# MCUs.net
KiCad netlist of a schematic drawn in Altium Designer
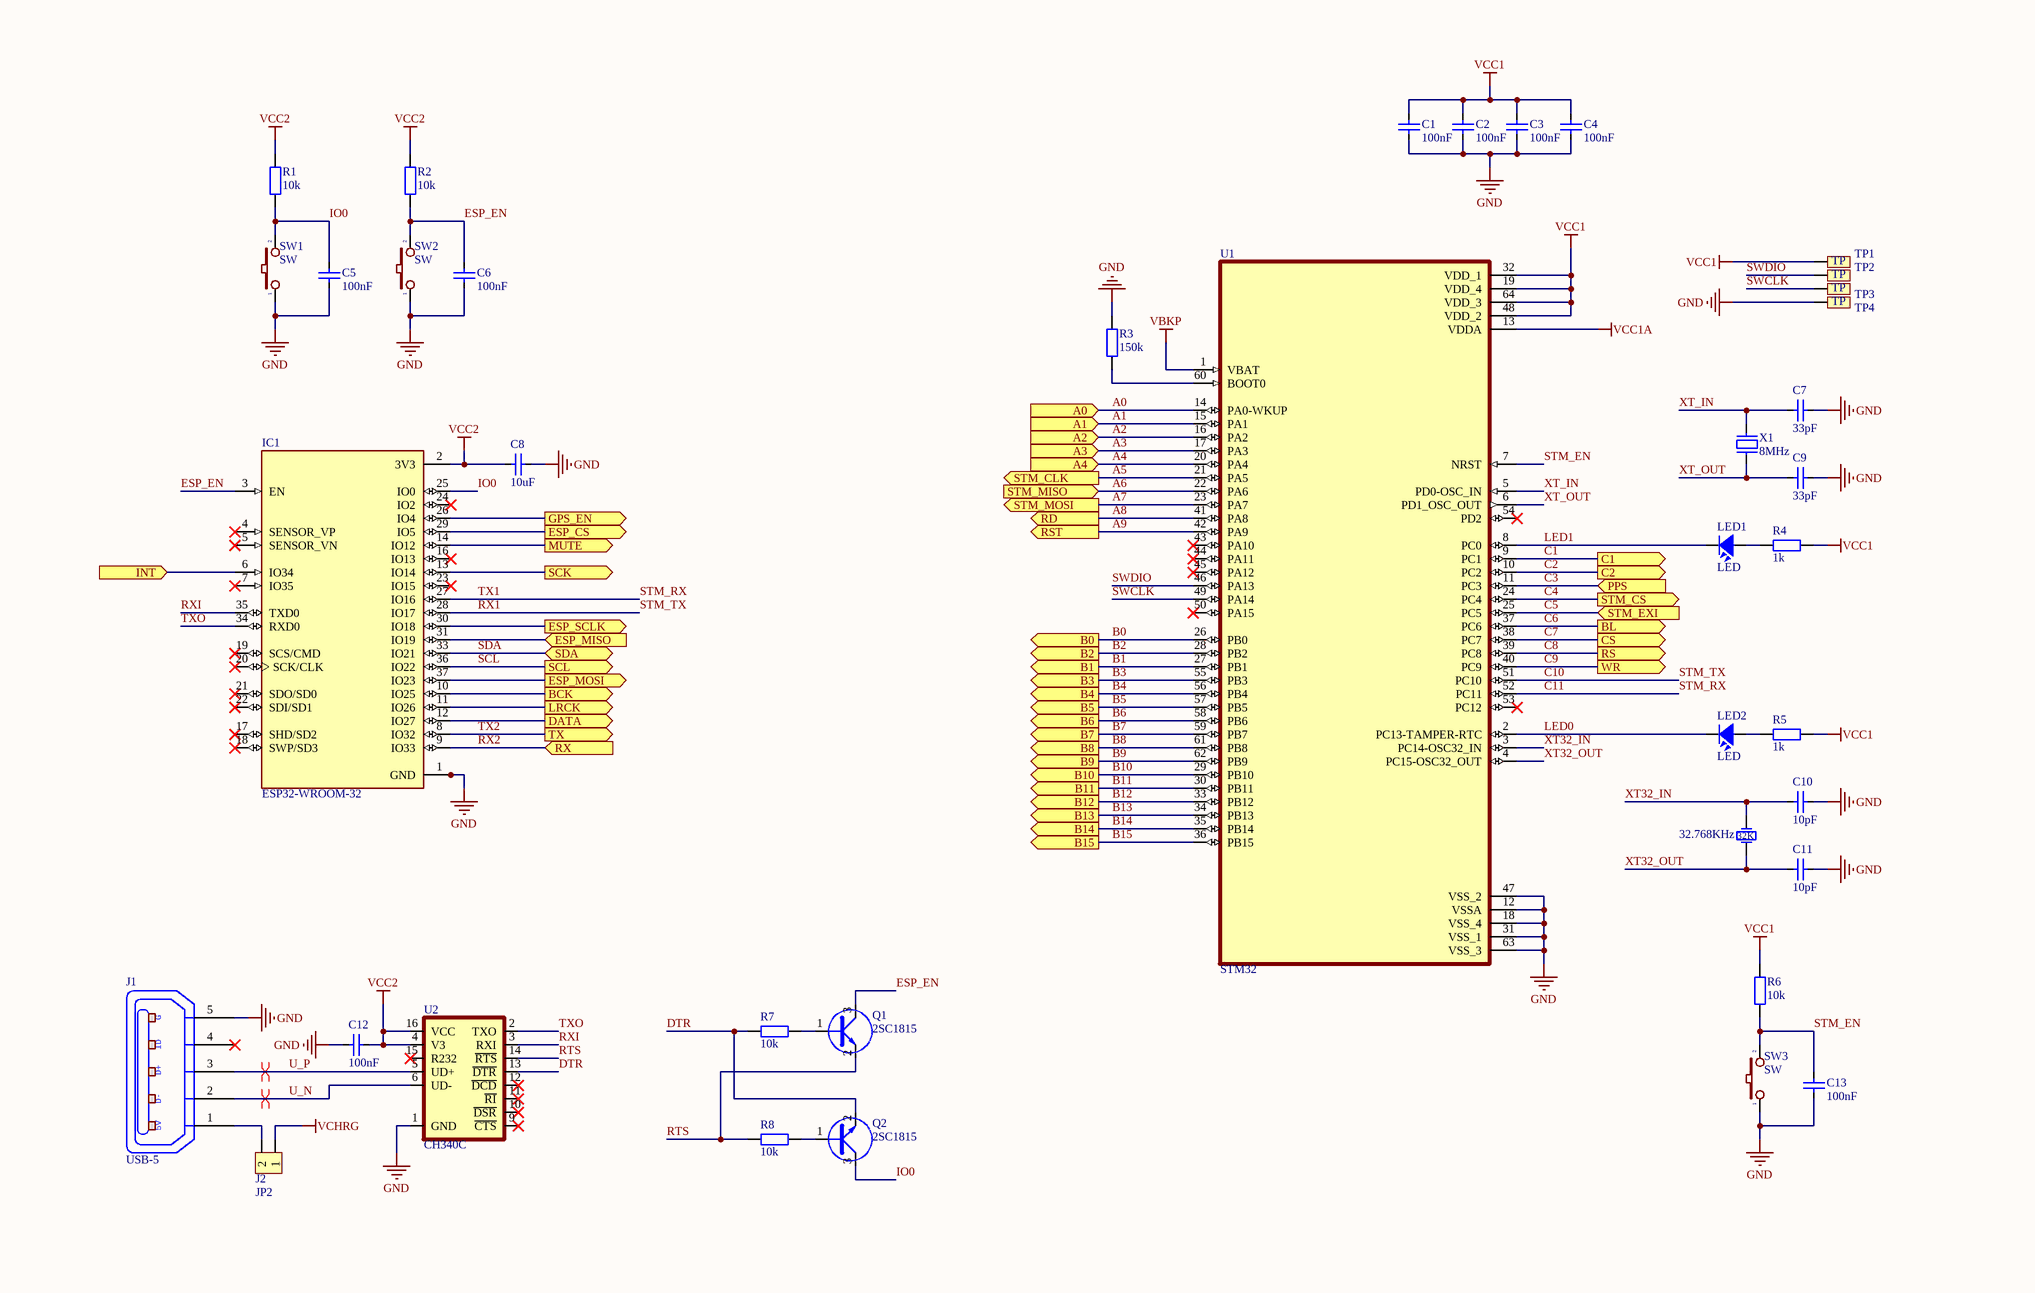
[diagram p0: MCUs.SchDoc]

(export (version "E")
  (design (tool "Eeschema 10.0.6"))
  (components
    (comp (ref "C1")
      (value "100nF")
      (footprint "CAP_0603")
      (description "Capacitor")
      (fields (field (name "PUBLISHER") "Altium Limited"))
      (libsource (lib "My Library") (part "CapSMD"))
    )
    (comp (ref "C2")
      (value "100nF")
      (footprint "CAP_0603")
      (description "Capacitor")
      (fields (field (name "PUBLISHER") "Altium Limited"))
      (libsource (lib "My Library") (part "CapSMD"))
    )
    (comp (ref "C3")
      (value "100nF")
      (footprint "CAP_0603")
      (description "Capacitor")
      (fields (field (name "PUBLISHER") "Altium Limited"))
      (libsource (lib "My Library") (part "CapSMD"))
    )
    (comp (ref "C4")
      (value "100nF")
      (footprint "CAP_0603")
      (description "Capacitor")
      (fields (field (name "PUBLISHER") "Altium Limited"))
      (libsource (lib "My Library") (part "CapSMD"))
    )
    (comp (ref "C5")
      (value "100nF")
      (footprint "CAP_0603")
      (description "Capacitor")
      (fields (field (name "PUBLISHER") "Altium Limited"))
      (libsource (lib "My Library") (part "CapSMD"))
    )
    (comp (ref "C6")
      (value "100nF")
      (footprint "CAP_0603")
      (description "Capacitor")
      (fields (field (name "PUBLISHER") "Altium Limited"))
      (libsource (lib "My Library") (part "CapSMD"))
    )
    (comp (ref "C7")
      (value "33pF")
      (footprint "CAP_0603")
      (description "Capacitor")
      (fields (field (name "PUBLISHER") "Altium Limited"))
      (libsource (lib "My Library") (part "CapSMD"))
    )
    (comp (ref "C8")
      (value "10uF")
      (footprint "CAP_0603")
      (description "Capacitor")
      (fields (field (name "PUBLISHER") "Altium Limited"))
      (libsource (lib "My Library") (part "CapSMD"))
    )
    (comp (ref "C9")
      (value "33pF")
      (footprint "CAP_0603")
      (description "Capacitor")
      (fields (field (name "PUBLISHER") "Altium Limited"))
      (libsource (lib "My Library") (part "CapSMD"))
    )
    (comp (ref "C10")
      (value "10pF")
      (footprint "CAP_0603")
      (description "Capacitor")
      (fields (field (name "PUBLISHER") "Altium Limited"))
      (libsource (lib "My Library") (part "CapSMD"))
    )
    (comp (ref "C11")
      (value "10pF")
      (footprint "CAP_0603")
      (description "Capacitor")
      (fields (field (name "PUBLISHER") "Altium Limited"))
      (libsource (lib "My Library") (part "CapSMD"))
    )
    (comp (ref "C12")
      (value "100nF")
      (footprint "CAP_0603")
      (description "Capacitor")
      (fields (field (name "PUBLISHER") "Altium Limited"))
      (libsource (lib "My Library") (part "CapSMD"))
    )
    (comp (ref "C13")
      (value "100nF")
      (footprint "CAP_0603")
      (description "Capacitor")
      (fields (field (name "PUBLISHER") "Altium Limited"))
      (libsource (lib "My Library") (part "CapSMD"))
    )
    (comp (ref "IC1")
      (value "ESP32-WROOM-32")
      (footprint "MODULE_ESP32-WROOM-32")
      (description "Bluetooth, WiFi Transceiver Module 2.4GHz ~ 2.5GHz Surface Mount")
      (fields (field (name "MF") "Espressif Systems") (field (name "DIGI-KEY_PART_NUMBER") "1904-1010-1-ND"))
      (libsource (lib "My Library") (part "ESP32-WROOM-32"))
    )
    (comp (ref "J1")
      (value "USB-5")
      (footprint "USB-M1")
      (fields
        (field (name "MANUFACTURER") "FCI")
        (field (name "MANUFACTURER PART NUMBER") "10118193-0001LF")
        (field (name ".CREATOR") "MM")
        (field (name ".CHECKED PCB") "RF")
        (field (name ".CHECKED SCH") "MM")
      )
      (libsource (lib "My Library") (part "USB-5"))
    )
    (comp (ref "J2")
      (value "JP2")
      (footprint "JP2-CLOSED")
      (description "WR-PHD 2.54 mm Angled Socket Header")
      (fields
        (field (name "MANUFACTURER") "Würth Elektronik eiSos GmbH")
        (field (name "PARTNO") "613002143121")
        (field (name "CREATED BY") "Karrer Zheng")
      )
      (libsource (lib "My Library") (part "JP2"))
    )
    (comp (ref "LED1")
      (value "LED")
      (footprint "LED-0805-Blue")
      (description "LED Single colour Green and Red")
      (libsource (lib "My Library") (part "LED"))
    )
    (comp (ref "LED2")
      (value "LED")
      (footprint "LED-0805-Green")
      (description "LED Single colour Green and Red")
      (libsource (lib "My Library") (part "LED"))
    )
    (comp (ref "Q1")
      (value "2SC1815")
      (footprint "SOT23D")
      (description "NPN 600mW, ECB")
      (libsource (lib "") (part "C1815_1"))
    )
    (comp (ref "Q2")
      (value "2SC1815")
      (footprint "SOT23D")
      (description "NPN 600mW, ECB")
      (libsource (lib "My Library") (part "C1815"))
    )
    (comp (ref "R1")
      (value "10k")
      (footprint "RES-SMD-0603")
      (description "Resistor SMD")
      (fields
        (field (name "MANUFACTURER") "Generic Components")
        (field (name "PUBLISHER") "Altium Hobart Technology Centre")
      )
      (libsource (lib "My Library") (part "Resistor - SMD"))
    )
    (comp (ref "R2")
      (value "10k")
      (footprint "RES-SMD-0603")
      (description "Resistor SMD")
      (fields
        (field (name "MANUFACTURER") "Generic Components")
        (field (name "PUBLISHER") "Altium Hobart Technology Centre")
      )
      (libsource (lib "My Library") (part "Resistor - SMD"))
    )
    (comp (ref "R3")
      (value "150k")
      (footprint "RES-SMD-0603")
      (description "Resistor SMD")
      (fields
        (field (name "MANUFACTURER") "Generic Components")
        (field (name "PUBLISHER") "Altium Hobart Technology Centre")
      )
      (libsource (lib "My Library") (part "Resistor - SMD"))
    )
    (comp (ref "R4")
      (value "1k")
      (footprint "RES-SMD-0603")
      (description "Resistor SMD")
      (fields
        (field (name "MANUFACTURER") "Generic Components")
        (field (name "PUBLISHER") "Altium Hobart Technology Centre")
      )
      (libsource (lib "My Library") (part "Resistor - SMD"))
    )
    (comp (ref "R5")
      (value "1k")
      (footprint "RES-SMD-0603")
      (description "Resistor SMD")
      (fields
        (field (name "MANUFACTURER") "Generic Components")
        (field (name "PUBLISHER") "Altium Hobart Technology Centre")
      )
      (libsource (lib "My Library") (part "Resistor - SMD"))
    )
    (comp (ref "R6")
      (value "10k")
      (footprint "RES-SMD-0603")
      (description "Resistor SMD")
      (fields
        (field (name "MANUFACTURER") "Generic Components")
        (field (name "PUBLISHER") "Altium Hobart Technology Centre")
      )
      (libsource (lib "My Library") (part "Resistor - SMD"))
    )
    (comp (ref "R7")
      (value "10k")
      (footprint "RES-SMD-0603")
      (description "Resistor SMD")
      (fields
        (field (name "MANUFACTURER") "Generic Components")
        (field (name "PUBLISHER") "Altium Hobart Technology Centre")
      )
      (libsource (lib "My Library") (part "Resistor - SMD"))
    )
    (comp (ref "R8")
      (value "10k")
      (footprint "RES-SMD-0603")
      (description "Resistor SMD")
      (fields
        (field (name "MANUFACTURER") "Generic Components")
        (field (name "PUBLISHER") "Altium Hobart Technology Centre")
      )
      (libsource (lib "My Library") (part "Resistor - SMD"))
    )
    (comp (ref "SW1")
      (value "SW")
      (footprint "SW 3x2x4")
      (description "Switch button 2 pin")
      (libsource (lib "My Library") (part "SW2"))
    )
    (comp (ref "SW2")
      (value "SW")
      (footprint "SW 3x2x4")
      (description "Switch button 2 pin")
      (libsource (lib "My Library") (part "SW2"))
    )
    (comp (ref "SW3")
      (value "SW")
      (footprint "SW 3x2x4")
      (description "Switch button 2 pin")
      (libsource (lib "My Library") (part "SW2"))
    )
    (comp (ref "TP1")
      (value "TP")
      (footprint "TP_SMD")
      (description "CONNECT 1")
      (libsource (lib "My Library") (part "TP"))
    )
    (comp (ref "TP2")
      (value "TP")
      (footprint "TP_SMD")
      (description "CONNECT 1")
      (libsource (lib "My Library") (part "TP"))
    )
    (comp (ref "TP3")
      (value "TP")
      (footprint "TP_SMD")
      (description "CONNECT 1")
      (libsource (lib "My Library") (part "TP"))
    )
    (comp (ref "TP4")
      (value "TP")
      (footprint "TP_SMD")
      (description "CONNECT 1")
      (libsource (lib "My Library") (part "TP"))
    )
    (comp (ref "U1")
      (value "STM32")
      (footprint "LQFP 64")
      (description "STM32 ARM-based 32-bit MCU 72MHz 256KB")
      (libsource (lib "My Library") (part "STM32F103RCT6"))
    )
    (comp (ref "U2")
      (value "CH340C")
      (footprint "SOP-16")
      (description "USB to serial chip CH340")
      (fields (field (name "MF") "WCH"))
      (libsource (lib "My Library") (part "CH340C"))
    )
    (comp (ref "X1")
      (value "8MHz")
      (footprint "XT2")
      (description "Crystal For all Crystal 2pin.")
      (libsource (lib "My Library") (part "XT2"))
    )
    (comp (ref "Y1")
      (value "32.768KHz")
      (footprint "XTAL32K")
      (description "Crystal Oscillator")
      (fields (field (name "PUBLISHER") "Altium Limited"))
      (libsource (lib "My Library") (part "XTAL/32KHz"))
    )
  )
  (nets
    (net (code "1") (name "/A0") (class "Default")
      (node (ref "U1") (pin "14") (pinfunction "PA0-WKUP_14") (pintype "bidirectional"))
    )
    (net (code "2") (name "/A1") (class "Default")
      (node (ref "U1") (pin "15") (pinfunction "PA1_15") (pintype "bidirectional"))
    )
    (net (code "3") (name "/A2") (class "Default")
      (node (ref "U1") (pin "16") (pinfunction "PA2_16") (pintype "bidirectional"))
    )
    (net (code "4") (name "/A3") (class "Default")
      (node (ref "U1") (pin "17") (pinfunction "PA3_17") (pintype "bidirectional"))
    )
    (net (code "5") (name "/A4") (class "Default")
      (node (ref "U1") (pin "20") (pinfunction "PA4_20") (pintype "bidirectional"))
    )
    (net (code "6") (name "/A5") (class "Default")
      (node (ref "U1") (pin "21") (pinfunction "PA5_21") (pintype "bidirectional"))
    )
    (net (code "7") (name "/A6") (class "Default")
      (node (ref "U1") (pin "22") (pinfunction "PA6_22") (pintype "bidirectional"))
    )
    (net (code "8") (name "/A7") (class "Default")
      (node (ref "U1") (pin "23") (pinfunction "PA7_23") (pintype "bidirectional"))
    )
    (net (code "9") (name "/A8") (class "Default")
      (node (ref "U1") (pin "41") (pinfunction "PA8_41") (pintype "bidirectional"))
    )
    (net (code "10") (name "/A9") (class "Default")
      (node (ref "U1") (pin "42") (pinfunction "PA9_42") (pintype "bidirectional"))
    )
    (net (code "11") (name "/B0") (class "Default")
      (node (ref "U1") (pin "26") (pinfunction "PB0_26") (pintype "bidirectional"))
    )
    (net (code "12") (name "/B1") (class "Default")
      (node (ref "U1") (pin "27") (pinfunction "PB1_27") (pintype "bidirectional"))
    )
    (net (code "13") (name "/B2") (class "Default")
      (node (ref "U1") (pin "28") (pinfunction "PB2_28") (pintype "bidirectional"))
    )
    (net (code "14") (name "/B3") (class "Default")
      (node (ref "U1") (pin "55") (pinfunction "PB3_55") (pintype "bidirectional"))
    )
    (net (code "15") (name "/B4") (class "Default")
      (node (ref "U1") (pin "56") (pinfunction "PB4_56") (pintype "bidirectional"))
    )
    (net (code "16") (name "/B5") (class "Default")
      (node (ref "U1") (pin "57") (pinfunction "PB5_57") (pintype "bidirectional"))
    )
    (net (code "17") (name "/B6") (class "Default")
      (node (ref "U1") (pin "58") (pinfunction "PB6_58") (pintype "bidirectional"))
    )
    (net (code "18") (name "/B7") (class "Default")
      (node (ref "U1") (pin "59") (pinfunction "PB7_59") (pintype "bidirectional"))
    )
    (net (code "19") (name "/B8") (class "Default")
      (node (ref "U1") (pin "61") (pinfunction "PB8_61") (pintype "bidirectional"))
    )
    (net (code "20") (name "/B9") (class "Default")
      (node (ref "U1") (pin "62") (pinfunction "PB9_62") (pintype "bidirectional"))
    )
    (net (code "21") (name "/B10") (class "Default")
      (node (ref "U1") (pin "29") (pinfunction "PB10_29") (pintype "bidirectional"))
    )
    (net (code "22") (name "/B11") (class "Default")
      (node (ref "U1") (pin "30") (pinfunction "PB11_30") (pintype "bidirectional"))
    )
    (net (code "23") (name "/B12") (class "Default")
      (node (ref "U1") (pin "33") (pinfunction "PB12_33") (pintype "bidirectional"))
    )
    (net (code "24") (name "/B13") (class "Default")
      (node (ref "U1") (pin "34") (pinfunction "PB13_34") (pintype "bidirectional"))
    )
    (net (code "25") (name "/B14") (class "Default")
      (node (ref "U1") (pin "35") (pinfunction "PB14_35") (pintype "bidirectional"))
    )
    (net (code "26") (name "/B15") (class "Default")
      (node (ref "U1") (pin "36") (pinfunction "PB15_36") (pintype "bidirectional"))
    )
    (net (code "27") (name "/BCK") (class "Default")
      (node (ref "IC1") (pin "10") (pinfunction "IO25_10") (pintype "bidirectional"))
    )
    (net (code "28") (name "/C1") (class "Default")
      (node (ref "U1") (pin "9") (pinfunction "PC1_9") (pintype "bidirectional"))
    )
    (net (code "29") (name "/C2") (class "Default")
      (node (ref "U1") (pin "10") (pinfunction "PC2_10") (pintype "bidirectional"))
    )
    (net (code "30") (name "/C3") (class "Default")
      (node (ref "U1") (pin "11") (pinfunction "PC3_11") (pintype "bidirectional"))
    )
    (net (code "31") (name "/C4") (class "Default")
      (node (ref "U1") (pin "24") (pinfunction "PC4_24") (pintype "bidirectional"))
    )
    (net (code "32") (name "/C5") (class "Default")
      (node (ref "U1") (pin "25") (pinfunction "PC5_25") (pintype "bidirectional"))
    )
    (net (code "33") (name "/C6") (class "Default")
      (node (ref "U1") (pin "37") (pinfunction "PC6_37") (pintype "bidirectional"))
    )
    (net (code "34") (name "/C7") (class "Default")
      (node (ref "U1") (pin "38") (pinfunction "PC7_38") (pintype "bidirectional"))
    )
    (net (code "35") (name "/C8") (class "Default")
      (node (ref "U1") (pin "39") (pinfunction "PC8_39") (pintype "bidirectional"))
    )
    (net (code "36") (name "/C9") (class "Default")
      (node (ref "U1") (pin "40") (pinfunction "PC9_40") (pintype "bidirectional"))
    )
    (net (code "37") (name "/C10") (class "Default")
      (node (ref "IC1") (pin "28") (pinfunction "IO17_28") (pintype "bidirectional"))
      (node (ref "U1") (pin "51") (pinfunction "PC10_51") (pintype "bidirectional"))
    )
    (net (code "38") (name "/C11") (class "Default")
      (node (ref "IC1") (pin "27") (pinfunction "IO16_27") (pintype "bidirectional"))
      (node (ref "U1") (pin "52") (pinfunction "PC11_52") (pintype "bidirectional"))
    )
    (net (code "39") (name "/DATA") (class "Default")
      (node (ref "IC1") (pin "12") (pinfunction "IO27_12") (pintype "bidirectional"))
    )
    (net (code "40") (name "/DTR") (class "Default")
      (node (ref "Q2") (pin "2") (pinfunction "E_2") (pintype "passive"))
      (node (ref "R7") (pin "2") (pinfunction "2_2") (pintype "passive"))
      (node (ref "U2") (pin "13") (pinfunction "~{DTR}_13") (pintype "bidirectional"))
    )
    (net (code "41") (name "/ESP_CS") (class "Default")
      (node (ref "IC1") (pin "29") (pinfunction "IO5_29") (pintype "bidirectional"))
    )
    (net (code "42") (name "/ESP_EN") (class "Default")
      (node (ref "C6") (pin "1") (pinfunction "1_1") (pintype "passive"))
      (node (ref "IC1") (pin "3") (pinfunction "EN_3") (pintype "input"))
      (node (ref "Q1") (pin "3") (pinfunction "C_3") (pintype "passive"))
      (node (ref "R2") (pin "1") (pinfunction "1_1") (pintype "passive"))
      (node (ref "SW2") (pin "2") (pinfunction "2_2") (pintype "passive"))
    )
    (net (code "43") (name "/ESP_MISO") (class "Default")
      (node (ref "IC1") (pin "31") (pinfunction "IO19_31") (pintype "bidirectional"))
    )
    (net (code "44") (name "/ESP_MOSI") (class "Default")
      (node (ref "IC1") (pin "37") (pinfunction "IO23_37") (pintype "bidirectional"))
    )
    (net (code "45") (name "/ESP_SCLK") (class "Default")
      (node (ref "IC1") (pin "30") (pinfunction "IO18_30") (pintype "bidirectional"))
    )
    (net (code "46") (name "/GPS_EN") (class "Default")
      (node (ref "IC1") (pin "26") (pinfunction "IO4_26") (pintype "bidirectional"))
    )
    (net (code "47") (name "/INT") (class "Default")
      (node (ref "IC1") (pin "6") (pinfunction "IO34_6") (pintype "input"))
    )
    (net (code "48") (name "/IO0") (class "Default")
      (node (ref "C5") (pin "1") (pinfunction "1_1") (pintype "passive"))
      (node (ref "IC1") (pin "25") (pinfunction "IO0_25") (pintype "bidirectional"))
      (node (ref "Q2") (pin "3") (pinfunction "C_3") (pintype "passive"))
      (node (ref "R1") (pin "1") (pinfunction "1_1") (pintype "passive"))
      (node (ref "SW1") (pin "2") (pinfunction "2_2") (pintype "passive"))
    )
    (net (code "49") (name "/LED0") (class "Default")
      (node (ref "LED2") (pin "2") (pinfunction "2_2") (pintype "passive"))
      (node (ref "U1") (pin "2") (pinfunction "PC13-TAMPER-RTC_2") (pintype "bidirectional"))
    )
    (net (code "50") (name "/LED1") (class "Default")
      (node (ref "LED1") (pin "2") (pinfunction "2_2") (pintype "passive"))
      (node (ref "U1") (pin "8") (pinfunction "PC0_8") (pintype "bidirectional"))
    )
    (net (code "51") (name "/LRCK") (class "Default")
      (node (ref "IC1") (pin "11") (pinfunction "IO26_11") (pintype "bidirectional"))
    )
    (net (code "52") (name "/MUTE") (class "Default")
      (node (ref "IC1") (pin "14") (pinfunction "IO12_14") (pintype "bidirectional"))
    )
    (net (code "53") (name "/RTS") (class "Default")
      (node (ref "Q1") (pin "2") (pinfunction "E_2") (pintype "passive"))
      (node (ref "R8") (pin "2") (pinfunction "2_2") (pintype "passive"))
      (node (ref "U2") (pin "14") (pinfunction "~{RTS}_14") (pintype "bidirectional"))
    )
    (net (code "54") (name "/RX2") (class "Default")
      (node (ref "IC1") (pin "9") (pinfunction "IO33_9") (pintype "bidirectional"))
    )
    (net (code "55") (name "/RXI") (class "Default")
      (node (ref "IC1") (pin "35") (pinfunction "TXD0_35") (pintype "bidirectional"))
      (node (ref "U2") (pin "3") (pinfunction "RXI_3") (pintype "bidirectional"))
    )
    (net (code "56") (name "/SCK") (class "Default")
      (node (ref "IC1") (pin "13") (pinfunction "IO14_13") (pintype "bidirectional"))
    )
    (net (code "57") (name "/SCL") (class "Default")
      (node (ref "IC1") (pin "36") (pinfunction "IO22_36") (pintype "bidirectional"))
    )
    (net (code "58") (name "/SDA") (class "Default")
      (node (ref "IC1") (pin "33") (pinfunction "IO21_33") (pintype "bidirectional"))
    )
    (net (code "59") (name "/STM_EN") (class "Default")
      (node (ref "C13") (pin "1") (pinfunction "1_1") (pintype "passive"))
      (node (ref "R6") (pin "1") (pinfunction "1_1") (pintype "passive"))
      (node (ref "SW3") (pin "2") (pinfunction "2_2") (pintype "passive"))
      (node (ref "U1") (pin "7") (pinfunction "NRST_7") (pintype "input"))
    )
    (net (code "60") (name "/SWCLK") (class "Default")
      (node (ref "TP3") (pin "1") (pinfunction "0_1") (pintype "passive"))
      (node (ref "U1") (pin "49") (pinfunction "PA14_49") (pintype "bidirectional"))
    )
    (net (code "61") (name "/SWDIO") (class "Default")
      (node (ref "TP2") (pin "1") (pinfunction "0_1") (pintype "passive"))
      (node (ref "U1") (pin "46") (pinfunction "PA13_46") (pintype "bidirectional"))
    )
    (net (code "62") (name "/TX2") (class "Default")
      (node (ref "IC1") (pin "8") (pinfunction "IO32_8") (pintype "bidirectional"))
    )
    (net (code "63") (name "/TXO") (class "Default")
      (node (ref "IC1") (pin "34") (pinfunction "RXD0_34") (pintype "bidirectional"))
      (node (ref "U2") (pin "2") (pinfunction "TXO_2") (pintype "bidirectional"))
    )
    (net (code "64") (name "/U_N") (class "Default")
      (node (ref "J1") (pin "2") (pinfunction "P2_2") (pintype "passive"))
      (node (ref "U2") (pin "6") (pinfunction "UD-_6") (pintype "bidirectional"))
    )
    (net (code "65") (name "/U_P") (class "Default")
      (node (ref "J1") (pin "3") (pinfunction "P3_3") (pintype "passive"))
      (node (ref "U2") (pin "5") (pinfunction "UD+_5") (pintype "bidirectional"))
    )
    (net (code "66") (name "/XT32_IN") (class "Default")
      (node (ref "C10") (pin "2") (pinfunction "2_2") (pintype "passive"))
      (node (ref "U1") (pin "3") (pinfunction "PC14-OSC32_IN_3") (pintype "bidirectional"))
      (node (ref "Y1") (pin "1") (pinfunction "OSC1_1") (pintype "passive"))
    )
    (net (code "67") (name "/XT32_OUT") (class "Default")
      (node (ref "C11") (pin "2") (pinfunction "2_2") (pintype "passive"))
      (node (ref "U1") (pin "4") (pinfunction "PC15-OSC32_OUT_4") (pintype "bidirectional"))
      (node (ref "Y1") (pin "2") (pinfunction "OSC2_2") (pintype "passive"))
    )
    (net (code "68") (name "/XT_IN") (class "Default")
      (node (ref "C7") (pin "2") (pinfunction "2_2") (pintype "passive"))
      (node (ref "U1") (pin "5") (pinfunction "PD0-OSC_IN_5") (pintype "input"))
      (node (ref "X1") (pin "2") (pinfunction "2_2") (pintype "passive"))
    )
    (net (code "69") (name "/XT_OUT") (class "Default")
      (node (ref "C9") (pin "2") (pinfunction "2_2") (pintype "passive"))
      (node (ref "U1") (pin "6") (pinfunction "PD1_OSC_OUT_6") (pintype "output"))
      (node (ref "X1") (pin "1") (pinfunction "1_1") (pintype "passive"))
    )
    (net (code "70") (name "GND") (class "Default")
      (node (ref "C1") (pin "2") (pinfunction "2_2") (pintype "passive"))
      (node (ref "C10") (pin "1") (pinfunction "1_1") (pintype "passive"))
      (node (ref "C11") (pin "1") (pinfunction "1_1") (pintype "passive"))
      (node (ref "C12") (pin "1") (pinfunction "1_1") (pintype "passive"))
      (node (ref "C13") (pin "2") (pinfunction "2_2") (pintype "passive"))
      (node (ref "C2") (pin "2") (pinfunction "2_2") (pintype "passive"))
      (node (ref "C3") (pin "2") (pinfunction "2_2") (pintype "passive"))
      (node (ref "C4") (pin "2") (pinfunction "2_2") (pintype "passive"))
      (node (ref "C5") (pin "2") (pinfunction "2_2") (pintype "passive"))
      (node (ref "C6") (pin "2") (pinfunction "2_2") (pintype "passive"))
      (node (ref "C7") (pin "1") (pinfunction "1_1") (pintype "passive"))
      (node (ref "C8") (pin "2") (pinfunction "2_2") (pintype "passive"))
      (node (ref "C9") (pin "1") (pinfunction "1_1") (pintype "passive"))
      (node (ref "IC1") (pin "1") (pinfunction "GND_1") (pintype "power_in"))
      (node (ref "IC1") (pin "15") (pinfunction "GND_15") (pintype "power_in"))
      (node (ref "IC1") (pin "38") (pinfunction "GND_38") (pintype "power_in"))
      (node (ref "IC1") (pin "39_1") (pinfunction "GND_39_1") (pintype "power_in"))
      (node (ref "IC1") (pin "39_10") (pinfunction "GND_39_10") (pintype "power_in"))
      (node (ref "IC1") (pin "39_11") (pinfunction "GND_39_11") (pintype "power_in"))
      (node (ref "IC1") (pin "39_12") (pinfunction "GND_39_12") (pintype "power_in"))
      (node (ref "IC1") (pin "39_13") (pinfunction "GND_39_13") (pintype "power_in"))
      (node (ref "IC1") (pin "39_14") (pinfunction "GND_39_14") (pintype "power_in"))
      (node (ref "IC1") (pin "39_15") (pinfunction "GND_39_15") (pintype "power_in"))
      (node (ref "IC1") (pin "39_16") (pinfunction "GND_39_16") (pintype "power_in"))
      (node (ref "IC1") (pin "39_17") (pinfunction "GND_39_17") (pintype "power_in"))
      (node (ref "IC1") (pin "39_18") (pinfunction "GND_39_18") (pintype "power_in"))
      (node (ref "IC1") (pin "39_19") (pinfunction "GND_39_19") (pintype "power_in"))
      (node (ref "IC1") (pin "39_2") (pinfunction "GND_39_2") (pintype "power_in"))
      (node (ref "IC1") (pin "39_20") (pinfunction "GND_39_20") (pintype "power_in"))
      (node (ref "IC1") (pin "39_21") (pinfunction "GND_39_21") (pintype "power_in"))
      (node (ref "IC1") (pin "39_3") (pinfunction "GND_39_3") (pintype "power_in"))
      (node (ref "IC1") (pin "39_4") (pinfunction "GND_39_4") (pintype "power_in"))
      (node (ref "IC1") (pin "39_5") (pinfunction "GND_39_5") (pintype "power_in"))
      (node (ref "IC1") (pin "39_6") (pinfunction "GND_39_6") (pintype "power_in"))
      (node (ref "IC1") (pin "39_7") (pinfunction "GND_39_7") (pintype "power_in"))
      (node (ref "IC1") (pin "39_8") (pinfunction "GND_39_8") (pintype "power_in"))
      (node (ref "IC1") (pin "39_9") (pinfunction "GND_39_9") (pintype "power_in"))
      (node (ref "J1") (pin "5") (pinfunction "P5_5") (pintype "passive"))
      (node (ref "R3") (pin "1") (pinfunction "1_1") (pintype "passive"))
      (node (ref "SW1") (pin "1") (pinfunction "1_1") (pintype "passive"))
      (node (ref "SW2") (pin "1") (pinfunction "1_1") (pintype "passive"))
      (node (ref "SW3") (pin "1") (pinfunction "1_1") (pintype "passive"))
      (node (ref "TP4") (pin "1") (pinfunction "0_1") (pintype "passive"))
      (node (ref "U1") (pin "12") (pinfunction "VSSA_12") (pintype "power_in"))
      (node (ref "U1") (pin "18") (pinfunction "VSS_4_18") (pintype "power_in"))
      (node (ref "U1") (pin "31") (pinfunction "VSS_1_31") (pintype "power_in"))
      (node (ref "U1") (pin "47") (pinfunction "VSS_2_47") (pintype "power_in"))
      (node (ref "U1") (pin "63") (pinfunction "VSS_3_63") (pintype "power_in"))
      (node (ref "U2") (pin "1") (pinfunction "GND_1") (pintype "bidirectional"))
    )
    (net (code "71") (name "Net-(J1-P1)") (class "Default")
      (node (ref "J1") (pin "1") (pinfunction "P1_1") (pintype "passive"))
      (node (ref "J2") (pin "2") (pinfunction "2_2") (pintype "passive"))
    )
    (net (code "72") (name "Net-(LED1-Pad1)") (class "Default")
      (node (ref "LED1") (pin "1") (pinfunction "1_1") (pintype "passive"))
      (node (ref "R4") (pin "2") (pinfunction "2_2") (pintype "passive"))
    )
    (net (code "73") (name "Net-(LED2-Pad1)") (class "Default")
      (node (ref "LED2") (pin "1") (pinfunction "1_1") (pintype "passive"))
      (node (ref "R5") (pin "2") (pinfunction "2_2") (pintype "passive"))
    )
    (net (code "74") (name "Net-(Q1-B)") (class "Default")
      (node (ref "Q1") (pin "1") (pinfunction "B_1") (pintype "passive"))
      (node (ref "R7") (pin "1") (pinfunction "1_1") (pintype "passive"))
    )
    (net (code "75") (name "Net-(Q2-B)") (class "Default")
      (node (ref "Q2") (pin "1") (pinfunction "B_1") (pintype "passive"))
      (node (ref "R8") (pin "1") (pinfunction "1_1") (pintype "passive"))
    )
    (net (code "76") (name "Net-(U1-BOOT0)") (class "Default")
      (node (ref "R3") (pin "2") (pinfunction "2_2") (pintype "passive"))
      (node (ref "U1") (pin "60") (pinfunction "BOOT0_60") (pintype "input"))
    )
    (net (code "77") (name "VBKP") (class "Default")
      (node (ref "U1") (pin "1") (pinfunction "VBAT_1") (pintype "input"))
    )
    (net (code "78") (name "VCC1") (class "Default")
      (node (ref "C1") (pin "1") (pinfunction "1_1") (pintype "passive"))
      (node (ref "C2") (pin "1") (pinfunction "1_1") (pintype "passive"))
      (node (ref "C3") (pin "1") (pinfunction "1_1") (pintype "passive"))
      (node (ref "C4") (pin "1") (pinfunction "1_1") (pintype "passive"))
      (node (ref "R4") (pin "1") (pinfunction "1_1") (pintype "passive"))
      (node (ref "R5") (pin "1") (pinfunction "1_1") (pintype "passive"))
      (node (ref "R6") (pin "2") (pinfunction "2_2") (pintype "passive"))
      (node (ref "TP1") (pin "1") (pinfunction "0_1") (pintype "passive"))
      (node (ref "U1") (pin "19") (pinfunction "VDD_4_19") (pintype "power_in"))
      (node (ref "U1") (pin "32") (pinfunction "VDD_1_32") (pintype "power_in"))
      (node (ref "U1") (pin "48") (pinfunction "VDD_2_48") (pintype "power_in"))
      (node (ref "U1") (pin "64") (pinfunction "VDD_3_64") (pintype "power_in"))
    )
    (net (code "79") (name "VCC1A") (class "Default")
      (node (ref "U1") (pin "13") (pinfunction "VDDA_13") (pintype "power_in"))
    )
    (net (code "80") (name "VCC2") (class "Default")
      (node (ref "C12") (pin "2") (pinfunction "2_2") (pintype "passive"))
      (node (ref "C8") (pin "1") (pinfunction "1_1") (pintype "passive"))
      (node (ref "IC1") (pin "2") (pinfunction "3V3_2") (pintype "power_in"))
      (node (ref "R1") (pin "2") (pinfunction "2_2") (pintype "passive"))
      (node (ref "R2") (pin "2") (pinfunction "2_2") (pintype "passive"))
      (node (ref "U2") (pin "16") (pinfunction "VCC_16") (pintype "bidirectional"))
      (node (ref "U2") (pin "4") (pinfunction "V3_4") (pintype "bidirectional"))
    )
    (net (code "81") (name "VCHRG") (class "Default")
      (node (ref "J2") (pin "1") (pinfunction "1_1") (pintype "passive"))
    )
    (net (code "82") (name "unconnected-(IC1-IO2-Pad24)") (class "Default")
      (node (ref "IC1") (pin "24") (pinfunction "IO2_24") (pintype "bidirectional+no_connect"))
    )
    (net (code "83") (name "unconnected-(IC1-IO13-Pad16)") (class "Default")
      (node (ref "IC1") (pin "16") (pinfunction "IO13_16") (pintype "bidirectional+no_connect"))
    )
    (net (code "84") (name "unconnected-(IC1-IO15-Pad23)") (class "Default")
      (node (ref "IC1") (pin "23") (pinfunction "IO15_23") (pintype "bidirectional+no_connect"))
    )
    (net (code "85") (name "unconnected-(IC1-IO35-Pad7)") (class "Default")
      (node (ref "IC1") (pin "7") (pinfunction "IO35_7") (pintype "input+no_connect"))
    )
    (net (code "86") (name "unconnected-(IC1-SCK{slash}CLK-Pad20)") (class "Default")
      (node (ref "IC1") (pin "20") (pinfunction "SCK/CLK_20") (pintype "bidirectional+no_connect"))
    )
    (net (code "87") (name "unconnected-(IC1-SCS{slash}CMD-Pad19)") (class "Default")
      (node (ref "IC1") (pin "19") (pinfunction "SCS/CMD_19") (pintype "bidirectional+no_connect"))
    )
    (net (code "88") (name "unconnected-(IC1-SDI{slash}SD1-Pad22)") (class "Default")
      (node (ref "IC1") (pin "22") (pinfunction "SDI/SD1_22") (pintype "bidirectional+no_connect"))
    )
    (net (code "89") (name "unconnected-(IC1-SDO{slash}SD0-Pad21)") (class "Default")
      (node (ref "IC1") (pin "21") (pinfunction "SDO/SD0_21") (pintype "bidirectional+no_connect"))
    )
    (net (code "90") (name "unconnected-(IC1-SENSOR_VN-Pad5)") (class "Default")
      (node (ref "IC1") (pin "5") (pinfunction "SENSOR_VN_5") (pintype "input+no_connect"))
    )
    (net (code "91") (name "unconnected-(IC1-SENSOR_VP-Pad4)") (class "Default")
      (node (ref "IC1") (pin "4") (pinfunction "SENSOR_VP_4") (pintype "input+no_connect"))
    )
    (net (code "92") (name "unconnected-(IC1-SHD{slash}SD2-Pad17)") (class "Default")
      (node (ref "IC1") (pin "17") (pinfunction "SHD/SD2_17") (pintype "bidirectional+no_connect"))
    )
    (net (code "93") (name "unconnected-(IC1-SWP{slash}SD3-Pad18)") (class "Default")
      (node (ref "IC1") (pin "18") (pinfunction "SWP/SD3_18") (pintype "bidirectional+no_connect"))
    )
    (net (code "94") (name "unconnected-(J1-P4-Pad4)") (class "Default")
      (node (ref "J1") (pin "4") (pinfunction "P4_4") (pintype "passive+no_connect"))
    )
    (net (code "95") (name "unconnected-(U1-PA10-Pad43)") (class "Default")
      (node (ref "U1") (pin "43") (pinfunction "PA10_43") (pintype "bidirectional+no_connect"))
    )
    (net (code "96") (name "unconnected-(U1-PA11-Pad44)") (class "Default")
      (node (ref "U1") (pin "44") (pinfunction "PA11_44") (pintype "bidirectional+no_connect"))
    )
    (net (code "97") (name "unconnected-(U1-PA12-Pad45)") (class "Default")
      (node (ref "U1") (pin "45") (pinfunction "PA12_45") (pintype "bidirectional+no_connect"))
    )
    (net (code "98") (name "unconnected-(U1-PA15-Pad50)") (class "Default")
      (node (ref "U1") (pin "50") (pinfunction "PA15_50") (pintype "bidirectional+no_connect"))
    )
    (net (code "99") (name "unconnected-(U1-PC12-Pad53)") (class "Default")
      (node (ref "U1") (pin "53") (pinfunction "PC12_53") (pintype "bidirectional+no_connect"))
    )
    (net (code "100") (name "unconnected-(U1-PD2-Pad54)") (class "Default")
      (node (ref "U1") (pin "54") (pinfunction "PD2_54") (pintype "bidirectional+no_connect"))
    )
    (net (code "101") (name "unconnected-(U2-R232-Pad15)") (class "Default")
      (node (ref "U2") (pin "15") (pinfunction "R232_15") (pintype "bidirectional+no_connect"))
    )
    (net (code "102") (name "unconnected-(U2-~{CTS}-Pad9)") (class "Default")
      (node (ref "U2") (pin "9") (pinfunction "~{CTS}_9") (pintype "bidirectional+no_connect"))
    )
    (net (code "103") (name "unconnected-(U2-~{DCD}-Pad12)") (class "Default")
      (node (ref "U2") (pin "12") (pinfunction "~{DCD}_12") (pintype "bidirectional+no_connect"))
    )
    (net (code "104") (name "unconnected-(U2-~{DSR}-Pad10)") (class "Default")
      (node (ref "U2") (pin "10") (pinfunction "~{DSR}_10") (pintype "bidirectional+no_connect"))
    )
    (net (code "105") (name "unconnected-(U2-~{RI}-Pad11)") (class "Default")
      (node (ref "U2") (pin "11") (pinfunction "~{RI}_11") (pintype "bidirectional+no_connect"))
    )
  )
)
